# stx_rfm95.net
KiCad netlist of a schematic drawn in EAGLE
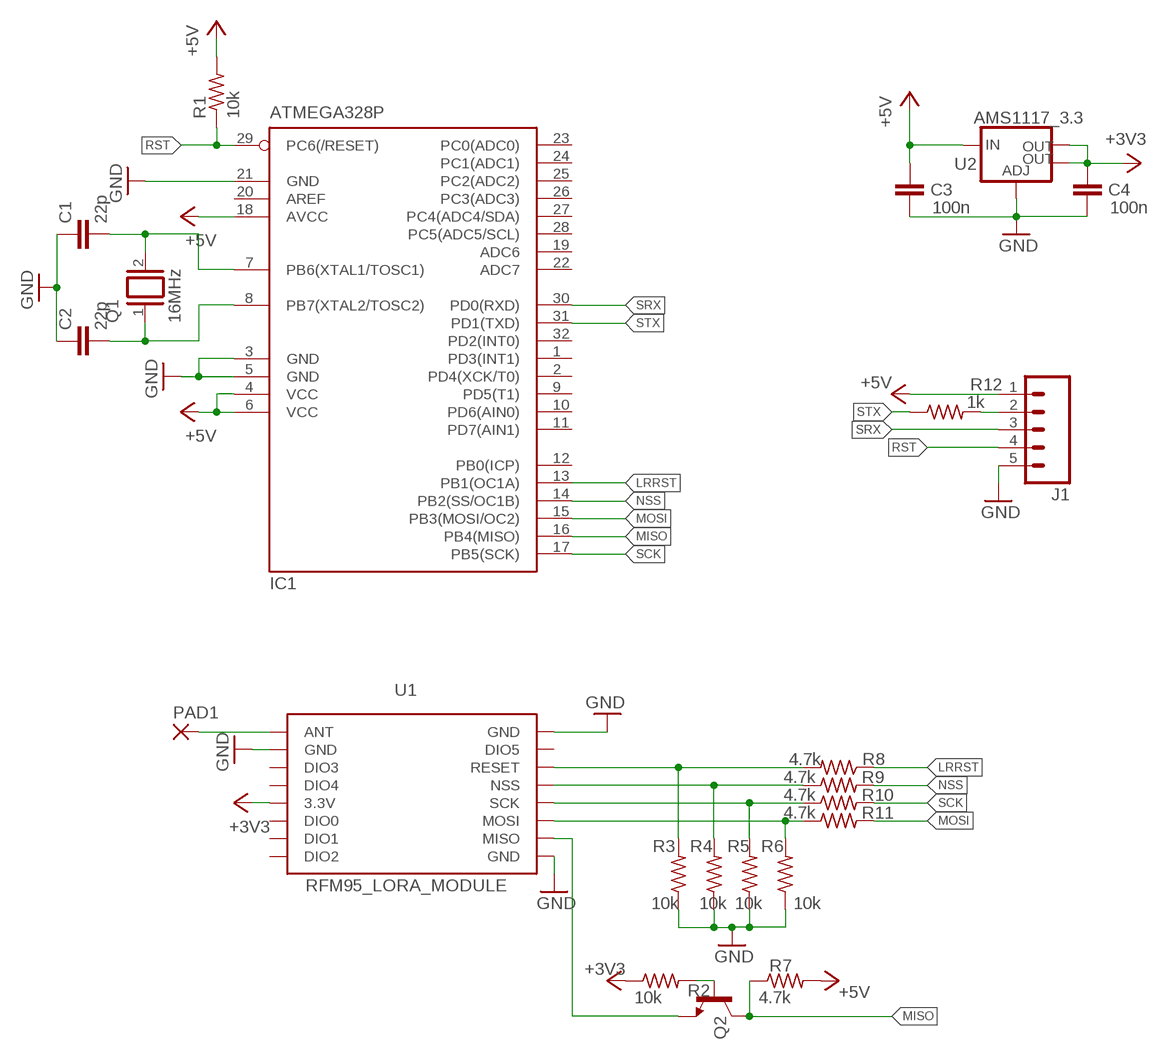
[diagram p0: schematic, sheet 1]

(export (version "E")
  (design (tool "Eeschema 10.0.6"))
  (components
    (comp (ref "C1")
      (value "22p")
      (footprint "eagle-import:C0805K")
      (libsource (lib "eagle-import") (part "C-EUC0805K"))
    )
    (comp (ref "C2")
      (value "22p")
      (footprint "eagle-import:C0805K")
      (libsource (lib "eagle-import") (part "C-EUC0805K"))
    )
    (comp (ref "C3")
      (value "100n")
      (footprint "eagle-import:C0805K")
      (libsource (lib "eagle-import") (part "C-EUC0805K"))
    )
    (comp (ref "C4")
      (value "100n")
      (footprint "eagle-import:C0805K")
      (libsource (lib "eagle-import") (part "C-EUC0805K"))
    )
    (comp (ref "IC1")
      (value "ATMEGA328P")
      (footprint "eagle-import:TQFP32-08")
      (fields (field (name "MPN") "ATMEGA8-16AU"))
      (libsource (lib "eagle-import") (part "MEGA8-AI"))
    )
    (comp (ref "J1")
      (value "M05PTH")
      (footprint "eagle-import:1X05")
      (libsource (lib "eagle-import") (part "M05PTH"))
    )
    (comp (ref "PAD1")
      (value "2,15/1,0")
      (footprint "eagle-import:2,15_1,0")
      (libsource (lib "eagle-import") (part "2,15/1,0"))
    )
    (comp (ref "Q1")
      (value "16MHz")
      (footprint "eagle-import:QS")
      (libsource (lib "eagle-import") (part "XTAL/S"))
    )
    (comp (ref "Q2")
      (value "BC817-16SMD")
      (footprint "eagle-import:SOT23-BEC")
      (libsource (lib "eagle-import") (part "BC817SMD-16"))
    )
    (comp (ref "R1")
      (value "10k")
      (footprint "eagle-import:R0805")
      (libsource (lib "eagle-import") (part "R-US_R0805"))
    )
    (comp (ref "R2")
      (value "10k")
      (footprint "eagle-import:R0805")
      (libsource (lib "eagle-import") (part "R-US_R0805"))
    )
    (comp (ref "R3")
      (value "10k")
      (footprint "eagle-import:R0805")
      (libsource (lib "eagle-import") (part "R-US_R0805"))
    )
    (comp (ref "R4")
      (value "10k")
      (footprint "eagle-import:R0805")
      (libsource (lib "eagle-import") (part "R-US_R0805"))
    )
    (comp (ref "R5")
      (value "10k")
      (footprint "eagle-import:R0805")
      (libsource (lib "eagle-import") (part "R-US_R0805"))
    )
    (comp (ref "R6")
      (value "10k")
      (footprint "eagle-import:R0805")
      (libsource (lib "eagle-import") (part "R-US_R0805"))
    )
    (comp (ref "R7")
      (value "4.7k")
      (footprint "eagle-import:R0805")
      (libsource (lib "eagle-import") (part "R-US_R0805"))
    )
    (comp (ref "R8")
      (value "4.7k")
      (footprint "eagle-import:R0805")
      (libsource (lib "eagle-import") (part "R-US_R0805"))
    )
    (comp (ref "R9")
      (value "4.7k")
      (footprint "eagle-import:R0805")
      (libsource (lib "eagle-import") (part "R-US_R0805"))
    )
    (comp (ref "R10")
      (value "4.7k")
      (footprint "eagle-import:R0805")
      (libsource (lib "eagle-import") (part "R-US_R0805"))
    )
    (comp (ref "R11")
      (value "4.7k")
      (footprint "eagle-import:R0805")
      (libsource (lib "eagle-import") (part "R-US_R0805"))
    )
    (comp (ref "R12")
      (value "1k")
      (footprint "eagle-import:R0805")
      (libsource (lib "eagle-import") (part "R-US_R0805"))
    )
    (comp (ref "U1")
      (value "RFM95_LORA_MODULE")
      (footprint "eagle-import:RFM95")
      (libsource (lib "eagle-import") (part "RFM95_LORA_MODULE"))
    )
    (comp (ref "U2")
      (value "AMS1117_3.3")
      (footprint "eagle-import:SOT223")
      (libsource (lib "eagle-import") (part "V_REG_LM1117SOT223"))
    )
  )
  (nets
    (net (code "1") (name "+3V3") (class "Default")
      (node (ref "C4") (pin "2") (pinfunction "2_2") (pintype "passive"))
      (node (ref "R2") (pin "1") (pinfunction "1_1") (pintype "passive"))
      (node (ref "U1") (pin "3.3V") (pinfunction "3.3V_3.3V") (pintype "bidirectional"))
      (node (ref "U2") (pin "2") (pinfunction "OUT_2") (pintype "output"))
      (node (ref "U2") (pin "4") (pinfunction "OUT_4") (pintype "output"))
    )
    (net (code "2") (name "+5V") (class "Default")
      (node (ref "C3") (pin "2") (pinfunction "2_2") (pintype "passive"))
      (node (ref "IC1") (pin "18") (pinfunction "AVCC_18") (pintype "power_in"))
      (node (ref "IC1") (pin "4") (pinfunction "VCC_4") (pintype "power_in"))
      (node (ref "IC1") (pin "6") (pinfunction "VCC_6") (pintype "power_in"))
      (node (ref "J1") (pin "1") (pinfunction "1_1") (pintype "passive"))
      (node (ref "R1") (pin "2") (pinfunction "2_2") (pintype "passive"))
      (node (ref "R7") (pin "2") (pinfunction "2_2") (pintype "passive"))
      (node (ref "U2") (pin "3") (pinfunction "IN_3") (pintype "input"))
    )
    (net (code "3") (name "/DIO3") (class "Default")
      (node (ref "U1") (pin "DIO3") (pinfunction "DIO3_DIO3") (pintype "power_in"))
    )
    (net (code "4") (name "GND") (class "Default")
      (node (ref "C1") (pin "1") (pinfunction "1_1") (pintype "passive"))
      (node (ref "C2") (pin "1") (pinfunction "1_1") (pintype "passive"))
      (node (ref "C3") (pin "1") (pinfunction "1_1") (pintype "passive"))
      (node (ref "C4") (pin "1") (pinfunction "1_1") (pintype "passive"))
      (node (ref "IC1") (pin "21") (pinfunction "GND_21") (pintype "power_in"))
      (node (ref "IC1") (pin "3") (pinfunction "GND_3") (pintype "power_in"))
      (node (ref "IC1") (pin "5") (pinfunction "GND_5") (pintype "power_in"))
      (node (ref "J1") (pin "5") (pinfunction "5_5") (pintype "passive"))
      (node (ref "R3") (pin "1") (pinfunction "1_1") (pintype "passive"))
      (node (ref "R4") (pin "1") (pinfunction "1_1") (pintype "passive"))
      (node (ref "R5") (pin "1") (pinfunction "1_1") (pintype "passive"))
      (node (ref "R6") (pin "1") (pinfunction "1_1") (pintype "passive"))
      (node (ref "U1") (pin "GND") (pinfunction "GND_GND") (pintype "power_in"))
      (node (ref "U1") (pin "GND@1") (pinfunction "GND_GND@1") (pintype "power_in"))
      (node (ref "U1") (pin "GND@2") (pinfunction "GND_GND@2") (pintype "power_in"))
      (node (ref "U2") (pin "1") (pinfunction "ADJ_1") (pintype "input"))
    )
    (net (code "5") (name "LRRST") (class "Default")
      (node (ref "IC1") (pin "13") (pinfunction "PB1(OC1A)_13") (pintype "bidirectional"))
      (node (ref "R8") (pin "1") (pinfunction "1_1") (pintype "passive"))
    )
    (net (code "6") (name "MISO") (class "Default")
      (node (ref "IC1") (pin "16") (pinfunction "PB4(MISO)_16") (pintype "bidirectional"))
      (node (ref "Q2") (pin "C") (pinfunction "C_C") (pintype "passive"))
      (node (ref "R7") (pin "1") (pinfunction "1_1") (pintype "passive"))
    )
    (net (code "7") (name "MOSI") (class "Default")
      (node (ref "IC1") (pin "15") (pinfunction "PB3(MOSI/OC2)_15") (pintype "bidirectional"))
      (node (ref "R11") (pin "2") (pinfunction "2_2") (pintype "passive"))
    )
    (net (code "8") (name "NSS") (class "Default")
      (node (ref "IC1") (pin "14") (pinfunction "PB2(SS/OC1B)_14") (pintype "bidirectional"))
      (node (ref "R9") (pin "2") (pinfunction "2_2") (pintype "passive"))
    )
    (net (code "9") (name "Net-(IC1-PB6(XTAL1{slash}TOSC1))") (class "Default")
      (node (ref "C1") (pin "2") (pinfunction "2_2") (pintype "passive"))
      (node (ref "IC1") (pin "7") (pinfunction "PB6(XTAL1/TOSC1)_7") (pintype "bidirectional"))
      (node (ref "Q1") (pin "2") (pinfunction "2_2") (pintype "passive"))
    )
    (net (code "10") (name "Net-(IC1-PB7(XTAL2{slash}TOSC2))") (class "Default")
      (node (ref "C2") (pin "2") (pinfunction "2_2") (pintype "passive"))
      (node (ref "IC1") (pin "8") (pinfunction "PB7(XTAL2/TOSC2)_8") (pintype "bidirectional"))
      (node (ref "Q1") (pin "1") (pinfunction "1_1") (pintype "passive"))
    )
    (net (code "11") (name "Net-(J1-Pad2)") (class "Default")
      (node (ref "J1") (pin "2") (pinfunction "2_2") (pintype "passive"))
      (node (ref "R12") (pin "2") (pinfunction "2_2") (pintype "passive"))
    )
    (net (code "12") (name "Net-(PAD1-P)") (class "Default")
      (node (ref "PAD1") (pin "1") (pinfunction "P_1") (pintype "passive"))
      (node (ref "U1") (pin "ANT") (pinfunction "ANT_ANT") (pintype "power_in"))
    )
    (net (code "13") (name "Net-(Q2-PadB)") (class "Default")
      (node (ref "Q2") (pin "B") (pinfunction "B_B") (pintype "passive"))
      (node (ref "R2") (pin "2") (pinfunction "2_2") (pintype "passive"))
    )
    (net (code "14") (name "Net-(Q2-PadE)") (class "Default")
      (node (ref "Q2") (pin "E") (pinfunction "E_E") (pintype "passive"))
      (node (ref "U1") (pin "MISO") (pinfunction "MISO_MISO") (pintype "bidirectional"))
    )
    (net (code "15") (name "Net-(R3-Pad2)") (class "Default")
      (node (ref "R3") (pin "2") (pinfunction "2_2") (pintype "passive"))
      (node (ref "R8") (pin "2") (pinfunction "2_2") (pintype "passive"))
      (node (ref "U1") (pin "RESET") (pinfunction "RESET_RESET") (pintype "bidirectional"))
    )
    (net (code "16") (name "Net-(R4-Pad2)") (class "Default")
      (node (ref "R4") (pin "2") (pinfunction "2_2") (pintype "passive"))
      (node (ref "R9") (pin "1") (pinfunction "1_1") (pintype "passive"))
      (node (ref "U1") (pin "NSS") (pinfunction "NSS_NSS") (pintype "bidirectional"))
    )
    (net (code "17") (name "Net-(R10-Pad1)") (class "Default")
      (node (ref "R10") (pin "1") (pinfunction "1_1") (pintype "passive"))
      (node (ref "R5") (pin "2") (pinfunction "2_2") (pintype "passive"))
      (node (ref "U1") (pin "SCK") (pinfunction "SCK_SCK") (pintype "bidirectional"))
    )
    (net (code "18") (name "Net-(R11-Pad1)") (class "Default")
      (node (ref "R11") (pin "1") (pinfunction "1_1") (pintype "passive"))
      (node (ref "R6") (pin "2") (pinfunction "2_2") (pintype "passive"))
      (node (ref "U1") (pin "MOSI") (pinfunction "MOSI_MOSI") (pintype "bidirectional"))
    )
    (net (code "19") (name "RST") (class "Default")
      (node (ref "IC1") (pin "29") (pinfunction "PC6(/RESET)_29") (pintype "bidirectional"))
      (node (ref "J1") (pin "4") (pinfunction "4_4") (pintype "passive"))
      (node (ref "R1") (pin "1") (pinfunction "1_1") (pintype "passive"))
    )
    (net (code "20") (name "SCK") (class "Default")
      (node (ref "IC1") (pin "17") (pinfunction "PB5(SCK)_17") (pintype "bidirectional"))
      (node (ref "R10") (pin "2") (pinfunction "2_2") (pintype "passive"))
    )
    (net (code "21") (name "SRX") (class "Default")
      (node (ref "IC1") (pin "30") (pinfunction "PD0(RXD)_30") (pintype "bidirectional"))
      (node (ref "J1") (pin "3") (pinfunction "3_3") (pintype "passive"))
    )
    (net (code "22") (name "STX") (class "Default")
      (node (ref "IC1") (pin "31") (pinfunction "PD1(TXD)_31") (pintype "bidirectional"))
      (node (ref "R12") (pin "1") (pinfunction "1_1") (pintype "passive"))
    )
    (net (code "23") (name "unconnected-(IC1-ADC6-Pad19)") (class "Default")
      (node (ref "IC1") (pin "19") (pinfunction "ADC6_19") (pintype "bidirectional"))
    )
    (net (code "24") (name "unconnected-(IC1-ADC7-Pad22)") (class "Default")
      (node (ref "IC1") (pin "22") (pinfunction "ADC7_22") (pintype "bidirectional"))
    )
    (net (code "25") (name "unconnected-(IC1-AREF-Pad20)") (class "Default")
      (node (ref "IC1") (pin "20") (pinfunction "AREF_20") (pintype "passive"))
    )
    (net (code "26") (name "unconnected-(IC1-PB0(ICP)-Pad12)") (class "Default")
      (node (ref "IC1") (pin "12") (pinfunction "PB0(ICP)_12") (pintype "bidirectional"))
    )
    (net (code "27") (name "unconnected-(IC1-PC0(ADC0)-Pad23)") (class "Default")
      (node (ref "IC1") (pin "23") (pinfunction "PC0(ADC0)_23") (pintype "bidirectional"))
    )
    (net (code "28") (name "unconnected-(IC1-PC1(ADC1)-Pad24)") (class "Default")
      (node (ref "IC1") (pin "24") (pinfunction "PC1(ADC1)_24") (pintype "bidirectional"))
    )
    (net (code "29") (name "unconnected-(IC1-PC2(ADC2)-Pad25)") (class "Default")
      (node (ref "IC1") (pin "25") (pinfunction "PC2(ADC2)_25") (pintype "bidirectional"))
    )
    (net (code "30") (name "unconnected-(IC1-PC3(ADC3)-Pad26)") (class "Default")
      (node (ref "IC1") (pin "26") (pinfunction "PC3(ADC3)_26") (pintype "bidirectional"))
    )
    (net (code "31") (name "unconnected-(IC1-PC4(ADC4{slash}SDA)-Pad27)") (class "Default")
      (node (ref "IC1") (pin "27") (pinfunction "PC4(ADC4/SDA)_27") (pintype "bidirectional"))
    )
    (net (code "32") (name "unconnected-(IC1-PC5(ADC5{slash}SCL)-Pad28)") (class "Default")
      (node (ref "IC1") (pin "28") (pinfunction "PC5(ADC5/SCL)_28") (pintype "bidirectional"))
    )
    (net (code "33") (name "unconnected-(IC1-PD2(INT0)-Pad32)") (class "Default")
      (node (ref "IC1") (pin "32") (pinfunction "PD2(INT0)_32") (pintype "bidirectional"))
    )
    (net (code "34") (name "unconnected-(IC1-PD3(INT1)-Pad1)") (class "Default")
      (node (ref "IC1") (pin "1") (pinfunction "PD3(INT1)_1") (pintype "bidirectional"))
    )
    (net (code "35") (name "unconnected-(IC1-PD4(XCK{slash}T0)-Pad2)") (class "Default")
      (node (ref "IC1") (pin "2") (pinfunction "PD4(XCK/T0)_2") (pintype "bidirectional"))
    )
    (net (code "36") (name "unconnected-(IC1-PD5(T1)-Pad9)") (class "Default")
      (node (ref "IC1") (pin "9") (pinfunction "PD5(T1)_9") (pintype "bidirectional"))
    )
    (net (code "37") (name "unconnected-(IC1-PD6(AIN0)-Pad10)") (class "Default")
      (node (ref "IC1") (pin "10") (pinfunction "PD6(AIN0)_10") (pintype "bidirectional"))
    )
    (net (code "38") (name "unconnected-(IC1-PD7(AIN1)-Pad11)") (class "Default")
      (node (ref "IC1") (pin "11") (pinfunction "PD7(AIN1)_11") (pintype "bidirectional"))
    )
    (net (code "39") (name "unconnected-(U1-PadDIO0)") (class "Default")
      (node (ref "U1") (pin "DIO0") (pinfunction "DIO0_DIO0") (pintype "bidirectional"))
    )
    (net (code "40") (name "unconnected-(U1-PadDIO1)") (class "Default")
      (node (ref "U1") (pin "DIO1") (pinfunction "DIO1_DIO1") (pintype "bidirectional"))
    )
    (net (code "41") (name "unconnected-(U1-PadDIO2)") (class "Default")
      (node (ref "U1") (pin "DIO2") (pinfunction "DIO2_DIO2") (pintype "bidirectional"))
    )
    (net (code "42") (name "unconnected-(U1-PadDIO4)") (class "Default")
      (node (ref "U1") (pin "DIO4") (pinfunction "DIO4_DIO4") (pintype "bidirectional"))
    )
    (net (code "43") (name "unconnected-(U1-PadDIO5)") (class "Default")
      (node (ref "U1") (pin "DIO5") (pinfunction "DIO5_DIO5") (pintype "bidirectional"))
    )
  )
)
